# CircleBatBoard.net
KiCad netlist of a schematic drawn in Altium Designer
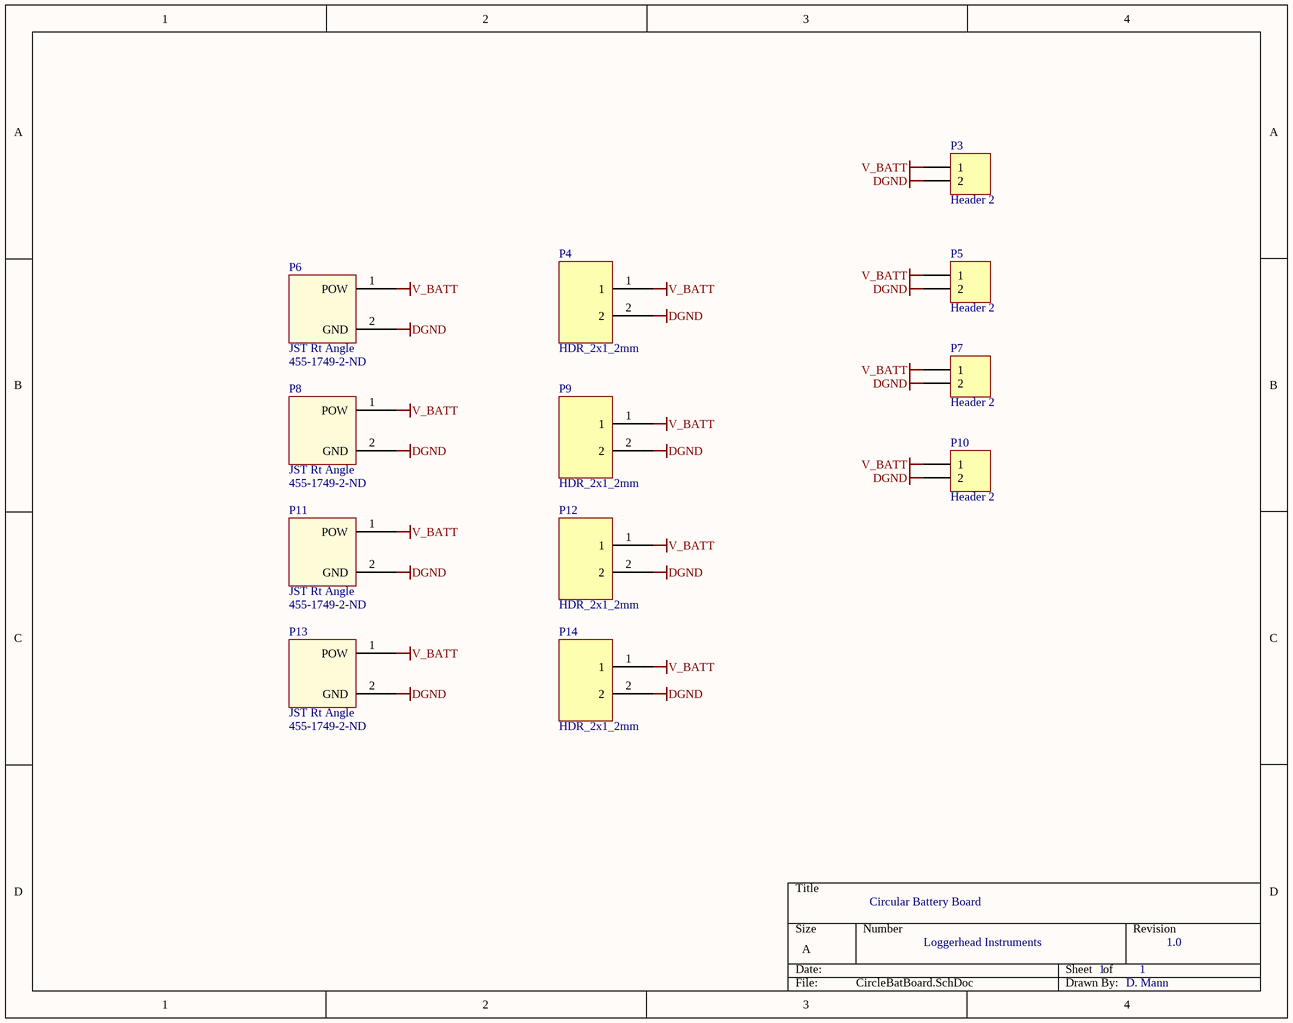
[diagram p0: CircleBatBoard.SchDoc]

(export (version "E")
  (design (tool "Eeschema 10.0.6"))
  (components
    (comp (ref "P3")
      (value "Header 2")
      (footprint "HDR1X2")
      (description "Header, 2-Pin")
      (fields (field (name "PUBLISHER") "Altium Limited"))
      (libsource (lib "Miscellaneous Connectors") (part "Header 2"))
    )
    (comp (ref "P4")
      (value "HDR_2x1_2mm")
      (footprint "HDR_2x1_2mm")
      (libsource (lib "Loggerhead") (part "HDR_2x1_2mm"))
    )
    (comp (ref "P5")
      (value "Header 2")
      (footprint "HDR1X2")
      (description "Header, 2-Pin")
      (fields (field (name "PUBLISHER") "Altium Limited"))
      (libsource (lib "Miscellaneous Connectors") (part "Header 2"))
    )
    (comp (ref "P6")
      (value "JST Rt Angle")
      (footprint "JST_2SMT")
      (fields (field (name "SUPPLIER PART NUMBER 1") "455-1749-2-ND"))
      (libsource (lib "Loggerhead") (part "JSTsmtRtAngle"))
    )
    (comp (ref "P7")
      (value "Header 2")
      (footprint "HDR1X2")
      (description "Header, 2-Pin")
      (fields (field (name "PUBLISHER") "Altium Limited"))
      (libsource (lib "Miscellaneous Connectors") (part "Header 2"))
    )
    (comp (ref "P8")
      (value "JST Rt Angle")
      (footprint "JST_2SMT")
      (fields (field (name "SUPPLIER PART NUMBER 1") "455-1749-2-ND"))
      (libsource (lib "Loggerhead") (part "JSTsmtRtAngle"))
    )
    (comp (ref "P9")
      (value "HDR_2x1_2mm")
      (footprint "HDR_2x1_2mm")
      (libsource (lib "Loggerhead") (part "HDR_2x1_2mm"))
    )
    (comp (ref "P10")
      (value "Header 2")
      (footprint "HDR1X2")
      (description "Header, 2-Pin")
      (fields (field (name "PUBLISHER") "Altium Limited"))
      (libsource (lib "Miscellaneous Connectors") (part "Header 2"))
    )
    (comp (ref "P11")
      (value "JST Rt Angle")
      (footprint "JST_2SMT")
      (fields (field (name "SUPPLIER PART NUMBER 1") "455-1749-2-ND"))
      (libsource (lib "Loggerhead") (part "JSTsmtRtAngle"))
    )
    (comp (ref "P12")
      (value "HDR_2x1_2mm")
      (footprint "HDR_2x1_2mm")
      (libsource (lib "Loggerhead") (part "HDR_2x1_2mm"))
    )
    (comp (ref "P13")
      (value "JST Rt Angle")
      (footprint "JST_2SMT")
      (fields (field (name "SUPPLIER PART NUMBER 1") "455-1749-2-ND"))
      (libsource (lib "Loggerhead") (part "JSTsmtRtAngle"))
    )
    (comp (ref "P14")
      (value "HDR_2x1_2mm")
      (footprint "HDR_2x1_2mm")
      (libsource (lib "Loggerhead") (part "HDR_2x1_2mm"))
    )
  )
  (nets
    (net (code "1") (name "DGND") (class "Default")
      (node (ref "P10") (pin "2") (pinfunction "2_2") (pintype "passive"))
      (node (ref "P11") (pin "2") (pinfunction "GND_2") (pintype "passive"))
      (node (ref "P12") (pin "2") (pinfunction "2_2") (pintype "passive"))
      (node (ref "P13") (pin "2") (pinfunction "GND_2") (pintype "passive"))
      (node (ref "P14") (pin "2") (pinfunction "2_2") (pintype "passive"))
      (node (ref "P3") (pin "2") (pinfunction "2_2") (pintype "passive"))
      (node (ref "P4") (pin "2") (pinfunction "2_2") (pintype "passive"))
      (node (ref "P5") (pin "2") (pinfunction "2_2") (pintype "passive"))
      (node (ref "P6") (pin "2") (pinfunction "GND_2") (pintype "passive"))
      (node (ref "P7") (pin "2") (pinfunction "2_2") (pintype "passive"))
      (node (ref "P8") (pin "2") (pinfunction "GND_2") (pintype "passive"))
      (node (ref "P9") (pin "2") (pinfunction "2_2") (pintype "passive"))
    )
    (net (code "2") (name "V_BATT") (class "Default")
      (node (ref "P10") (pin "1") (pinfunction "1_1") (pintype "passive"))
      (node (ref "P11") (pin "1") (pinfunction "POW_1") (pintype "passive"))
      (node (ref "P12") (pin "1") (pinfunction "1_1") (pintype "passive"))
      (node (ref "P13") (pin "1") (pinfunction "POW_1") (pintype "passive"))
      (node (ref "P14") (pin "1") (pinfunction "1_1") (pintype "passive"))
      (node (ref "P3") (pin "1") (pinfunction "1_1") (pintype "passive"))
      (node (ref "P4") (pin "1") (pinfunction "1_1") (pintype "passive"))
      (node (ref "P5") (pin "1") (pinfunction "1_1") (pintype "passive"))
      (node (ref "P6") (pin "1") (pinfunction "POW_1") (pintype "passive"))
      (node (ref "P7") (pin "1") (pinfunction "1_1") (pintype "passive"))
      (node (ref "P8") (pin "1") (pinfunction "POW_1") (pintype "passive"))
      (node (ref "P9") (pin "1") (pinfunction "1_1") (pintype "passive"))
    )
  )
)
